# RHT_Sensor_V2.net
KiCad netlist of a schematic drawn in EAGLE
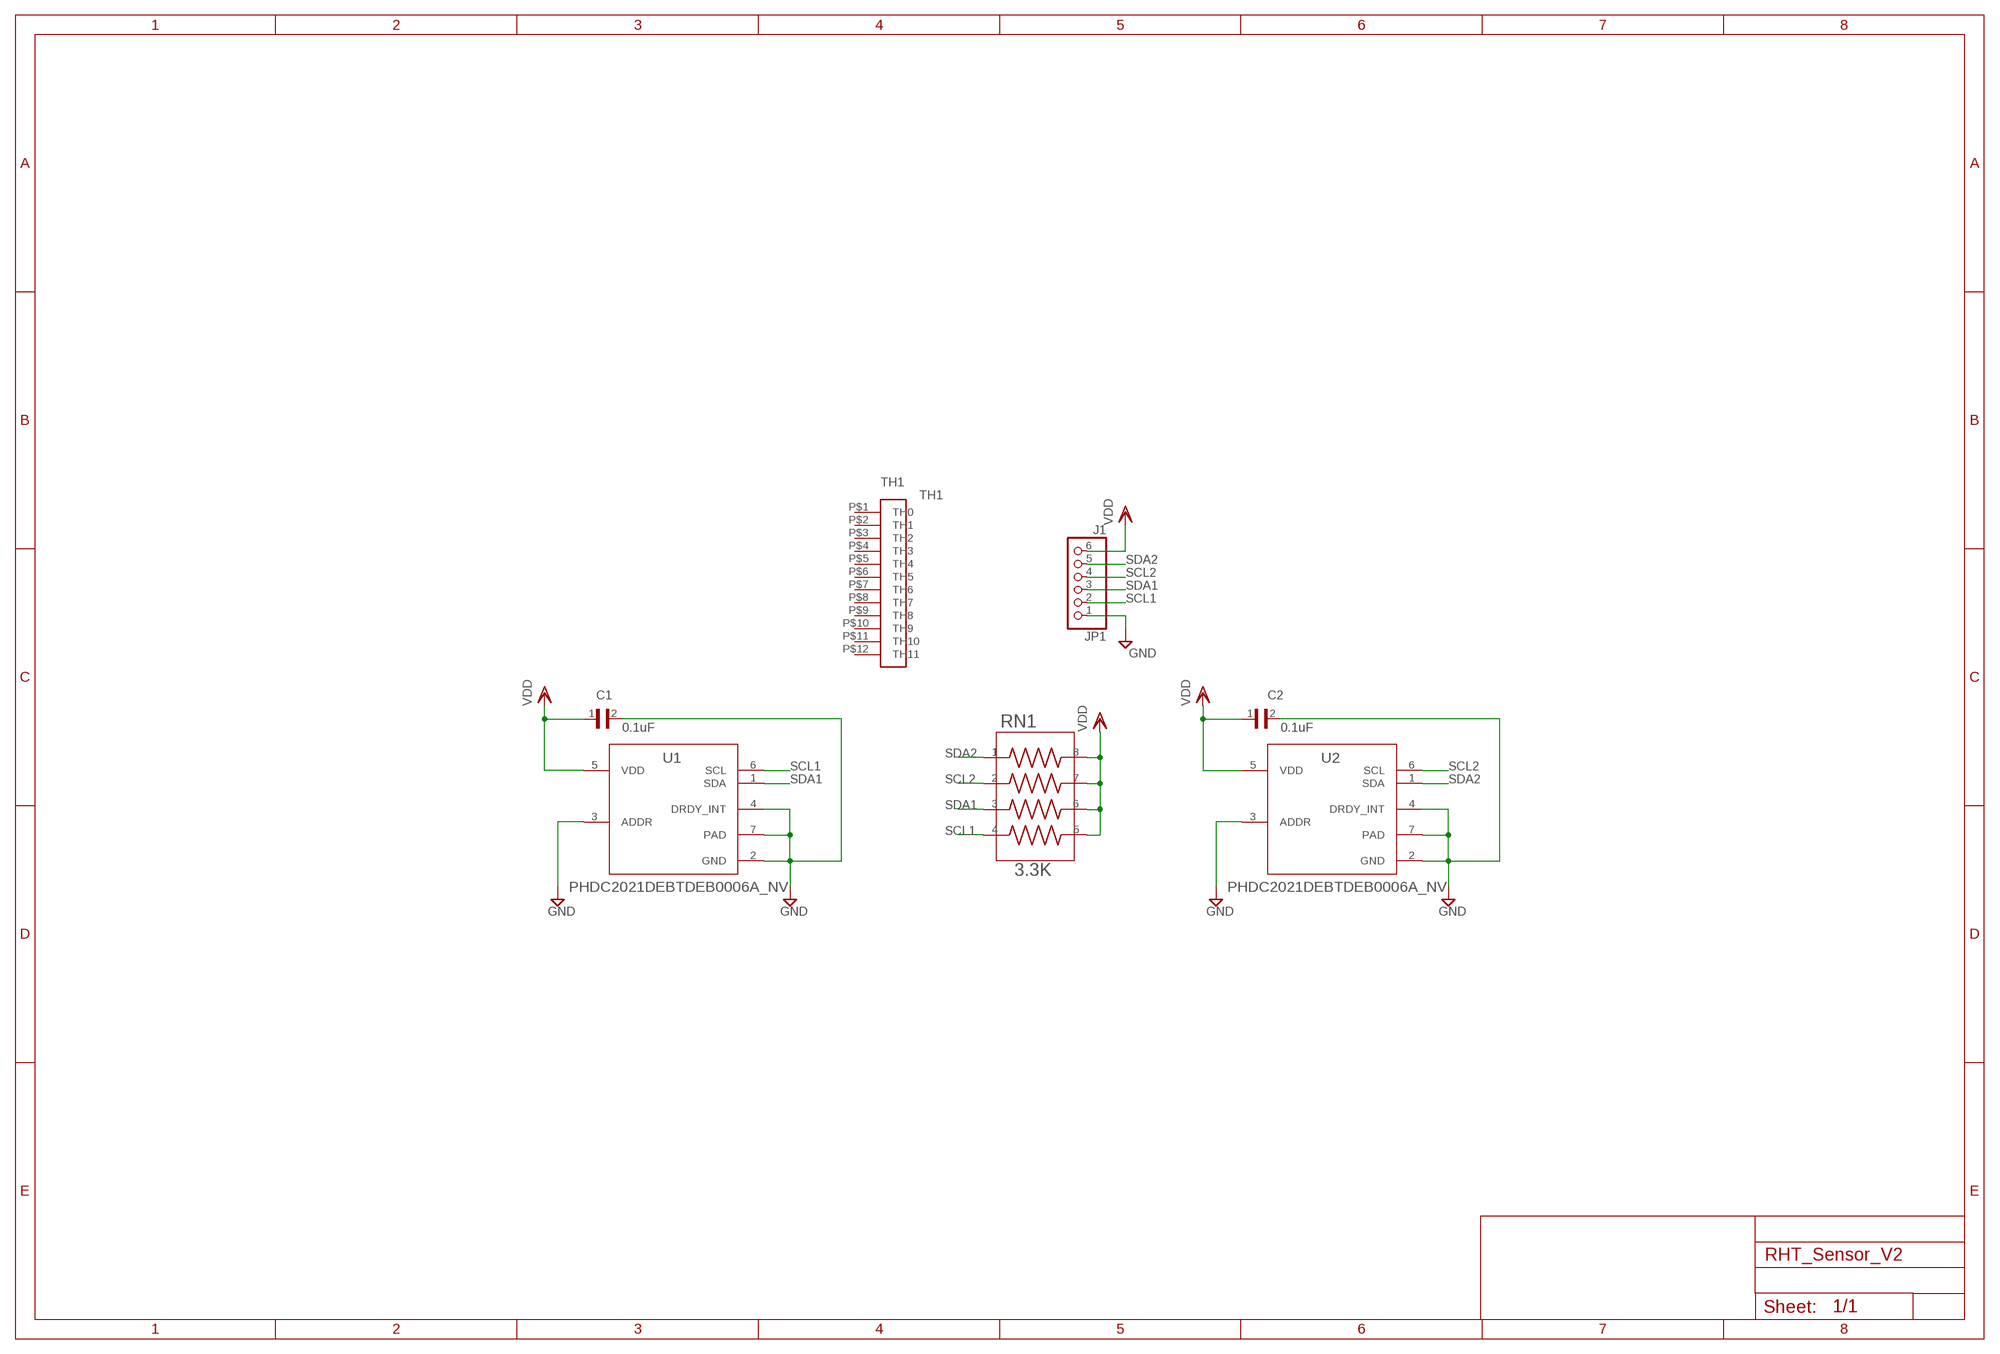
[diagram p0: schematic, sheet 1]

(export (version "E")
  (design (tool "Eeschema 10.0.6"))
  (components
    (comp (ref "C1")
      (value "0.1uF")
      (footprint "eagle-import:CAPC2012X94N")
      (fields (field (name "MF") "AVX") (field (name "MP") "08055C104KAT4A"))
      (libsource (lib "eagle-import") (part "08055C104KAT4A"))
    )
    (comp (ref "C2")
      (value "0.1uF")
      (footprint "eagle-import:CAPC2012X94N")
      (fields (field (name "MF") "AVX") (field (name "MP") "08055C104KAT4A"))
      (libsource (lib "eagle-import") (part "08055C104KAT4A"))
    )
    (comp (ref "JP1")
      (value "J1")
      (footprint "eagle-import:1X06")
      (libsource (lib "eagle-import") (part "PINHD-1X6"))
    )
    (comp (ref "RN1")
      (value "3.3K")
      (footprint "eagle-import:RESCAF80P320X160X60-8N")
      (fields (field (name "MANUFACTURER") "Bourns"))
      (libsource (lib "eagle-import") (part "CAY16-332J4LF"))
    )
    (comp (ref "TH1")
      (value "TH1")
      (footprint "eagle-import:1MM_HEADER_01X12")
      (libsource (lib "eagle-import") (part "1MM_HEADER-01X12"))
    )
    (comp (ref "U1")
      (value "PHDC2021DEBTDEB0006A_NV")
      (footprint "eagle-import:DEB0006A_NV")
      (fields
        (field (name "MANUFACTURER_PART_NUMBER") "PHDC2021DEBT")
        (field (name "COPYRIGHT") "Copyright (C) 2023 Ultra Librarian. All rights reserved.")
      )
      (libsource (lib "eagle-import") (part "PHDC2021DEBTDEB0006A_NV"))
    )
    (comp (ref "U2")
      (value "PHDC2021DEBTDEB0006A_NV")
      (footprint "eagle-import:DEB0006A_NV")
      (fields
        (field (name "MANUFACTURER_PART_NUMBER") "PHDC2021DEBT")
        (field (name "COPYRIGHT") "Copyright (C) 2023 Ultra Librarian. All rights reserved.")
      )
      (libsource (lib "eagle-import") (part "PHDC2021DEBTDEB0006A_NV"))
    )
  )
  (nets
    (net (code "1") (name "/SCL1") (class "Default")
      (node (ref "JP1") (pin "2") (pinfunction "2_2") (pintype "passive"))
      (node (ref "RN1") (pin "4") (pinfunction "4_4") (pintype "passive"))
      (node (ref "U1") (pin "6") (pinfunction "SCL_6") (pintype "open_collector"))
    )
    (net (code "2") (name "/SCL2") (class "Default")
      (node (ref "JP1") (pin "4") (pinfunction "4_4") (pintype "passive"))
      (node (ref "RN1") (pin "2") (pinfunction "2_2") (pintype "passive"))
      (node (ref "U2") (pin "6") (pinfunction "SCL_6") (pintype "open_collector"))
    )
    (net (code "3") (name "/SDA1") (class "Default")
      (node (ref "JP1") (pin "3") (pinfunction "3_3") (pintype "passive"))
      (node (ref "RN1") (pin "3") (pinfunction "3_3") (pintype "passive"))
      (node (ref "U1") (pin "1") (pinfunction "SDA_1") (pintype "bidirectional"))
    )
    (net (code "4") (name "/SDA2") (class "Default")
      (node (ref "JP1") (pin "5") (pinfunction "5_5") (pintype "passive"))
      (node (ref "RN1") (pin "1") (pinfunction "1_1") (pintype "passive"))
      (node (ref "U2") (pin "1") (pinfunction "SDA_1") (pintype "bidirectional"))
    )
    (net (code "5") (name "GND") (class "Default")
      (node (ref "C1") (pin "2") (pinfunction "2_2") (pintype "passive"))
      (node (ref "C2") (pin "2") (pinfunction "2_2") (pintype "passive"))
      (node (ref "JP1") (pin "1") (pinfunction "1_1") (pintype "passive"))
      (node (ref "U1") (pin "2") (pinfunction "GND_2") (pintype "power_in"))
      (node (ref "U1") (pin "3") (pinfunction "ADDR_3") (pintype "power_in"))
      (node (ref "U1") (pin "4") (pinfunction "DRDY_INT_4") (pintype "power_in"))
      (node (ref "U1") (pin "7") (pinfunction "PAD_7") (pintype "power_in"))
      (node (ref "U2") (pin "2") (pinfunction "GND_2") (pintype "power_in"))
      (node (ref "U2") (pin "3") (pinfunction "ADDR_3") (pintype "power_in"))
      (node (ref "U2") (pin "4") (pinfunction "DRDY_INT_4") (pintype "power_in"))
      (node (ref "U2") (pin "7") (pinfunction "PAD_7") (pintype "power_in"))
    )
    (net (code "6") (name "VDD") (class "Default")
      (node (ref "C1") (pin "1") (pinfunction "1_1") (pintype "passive"))
      (node (ref "C2") (pin "1") (pinfunction "1_1") (pintype "passive"))
      (node (ref "JP1") (pin "6") (pinfunction "6_6") (pintype "passive"))
      (node (ref "RN1") (pin "5") (pinfunction "5_5") (pintype "passive"))
      (node (ref "RN1") (pin "6") (pinfunction "6_6") (pintype "passive"))
      (node (ref "RN1") (pin "7") (pinfunction "7_7") (pintype "passive"))
      (node (ref "RN1") (pin "8") (pinfunction "8_8") (pintype "passive"))
      (node (ref "U1") (pin "5") (pinfunction "VDD_5") (pintype "power_in"))
      (node (ref "U2") (pin "5") (pinfunction "VDD_5") (pintype "power_in"))
    )
    (net (code "7") (name "unconnected-(TH1-TH0-PadP$1)") (class "Default")
      (node (ref "TH1") (pin "P$1") (pinfunction "TH0_P$1") (pintype "bidirectional"))
    )
    (net (code "8") (name "unconnected-(TH1-TH1-PadP$2)") (class "Default")
      (node (ref "TH1") (pin "P$2") (pinfunction "TH1_P$2") (pintype "bidirectional"))
    )
    (net (code "9") (name "unconnected-(TH1-TH2-PadP$3)") (class "Default")
      (node (ref "TH1") (pin "P$3") (pinfunction "TH2_P$3") (pintype "bidirectional"))
    )
    (net (code "10") (name "unconnected-(TH1-TH3-PadP$4)") (class "Default")
      (node (ref "TH1") (pin "P$4") (pinfunction "TH3_P$4") (pintype "bidirectional"))
    )
    (net (code "11") (name "unconnected-(TH1-TH4-PadP$5)") (class "Default")
      (node (ref "TH1") (pin "P$5") (pinfunction "TH4_P$5") (pintype "bidirectional"))
    )
    (net (code "12") (name "unconnected-(TH1-TH5-PadP$6)") (class "Default")
      (node (ref "TH1") (pin "P$6") (pinfunction "TH5_P$6") (pintype "bidirectional"))
    )
    (net (code "13") (name "unconnected-(TH1-TH6-PadP$7)") (class "Default")
      (node (ref "TH1") (pin "P$7") (pinfunction "TH6_P$7") (pintype "bidirectional"))
    )
    (net (code "14") (name "unconnected-(TH1-TH7-PadP$8)") (class "Default")
      (node (ref "TH1") (pin "P$8") (pinfunction "TH7_P$8") (pintype "bidirectional"))
    )
    (net (code "15") (name "unconnected-(TH1-TH8-PadP$9)") (class "Default")
      (node (ref "TH1") (pin "P$9") (pinfunction "TH8_P$9") (pintype "bidirectional"))
    )
    (net (code "16") (name "unconnected-(TH1-TH9-PadP$10)") (class "Default")
      (node (ref "TH1") (pin "P$10") (pinfunction "TH9_P$10") (pintype "bidirectional"))
    )
    (net (code "17") (name "unconnected-(TH1-TH10-PadP$11)") (class "Default")
      (node (ref "TH1") (pin "P$11") (pinfunction "TH10_P$11") (pintype "bidirectional"))
    )
    (net (code "18") (name "unconnected-(TH1-TH11-PadP$12)") (class "Default")
      (node (ref "TH1") (pin "P$12") (pinfunction "TH11_P$12") (pintype "bidirectional"))
    )
  )
)
